# Black_jr5.net
KiCad netlist of a schematic drawn in EAGLE
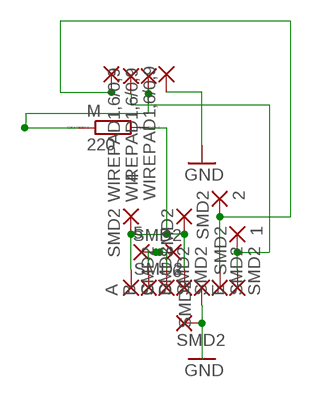
[diagram p0: schematic, sheet 1]

(export (version "E")
  (design (tool "Eeschema 10.0.6"))
  (components
    (comp (ref "+")
      (value "SMD2")
      (footprint "eagle-import:SMD1,27-2,54")
      (libsource (lib "eagle-import") (part "SMD2"))
    )
    (comp (ref "-")
      (value "SMD2")
      (footprint "eagle-import:SMD1,27-2,54")
      (libsource (lib "eagle-import") (part "SMD2"))
    )
    (comp (ref "--")
      (value "1,6/0,9")
      (footprint "eagle-import:1,6_0,9")
      (libsource (lib "eagle-import") (part "1,6/0,9"))
    )
    (comp (ref "---")
      (value "WIREPAD1,6/0,9")
      (footprint "eagle-import:1,6_0,9")
      (libsource (lib "eagle-import") (part "WIREPAD1,6/0,9"))
    )
    (comp (ref "----")
      (value "WIREPAD1,6/0,9")
      (footprint "eagle-import:1,6_0,9")
      (libsource (lib "eagle-import") (part "WIREPAD1,6/0,9"))
    )
    (comp (ref "-----")
      (value "WIREPAD1,6/0,9")
      (footprint "eagle-import:1,6_0,9")
      (libsource (lib "eagle-import") (part "WIREPAD1,6/0,9"))
    )
    (comp (ref "...")
      (value "SMD2")
      (footprint "eagle-import:SMD1,27-2,54")
      (libsource (lib "eagle-import") (part "SMD2"))
    )
    (comp (ref "1")
      (value "SMD2")
      (footprint "eagle-import:SMD1,27-2,54")
      (libsource (lib "eagle-import") (part "SMD2"))
    )
    (comp (ref "2")
      (value "SMD2")
      (footprint "eagle-import:SMD1,27-2,54")
      (libsource (lib "eagle-import") (part "SMD2"))
    )
    (comp (ref "4")
      (value "SMD2")
      (footprint "eagle-import:SMD1,27-2,54")
      (libsource (lib "eagle-import") (part "SMD2"))
    )
    (comp (ref "5")
      (value "SMD2")
      (footprint "eagle-import:SMD1,27-2,54")
      (libsource (lib "eagle-import") (part "SMD2"))
    )
    (comp (ref "6")
      (value "SMD2")
      (footprint "eagle-import:SMD1,27-2,54")
      (libsource (lib "eagle-import") (part "SMD2"))
    )
    (comp (ref "A")
      (value "SMD2")
      (footprint "eagle-import:SMD1,27-2,54")
      (libsource (lib "eagle-import") (part "SMD2"))
    )
    (comp (ref "B")
      (value "SMD2")
      (footprint "eagle-import:SMD1,27-2,54")
      (libsource (lib "eagle-import") (part "SMD2"))
    )
    (comp (ref "C")
      (value "SMD2")
      (footprint "eagle-import:SMD1,27-2,54")
      (libsource (lib "eagle-import") (part "SMD2"))
    )
    (comp (ref "D")
      (value "SMD2")
      (footprint "eagle-import:SMD1,27-2,54")
      (libsource (lib "eagle-import") (part "SMD2"))
    )
    (comp (ref "E")
      (value "SMD2")
      (footprint "eagle-import:SMD1,27-2,54")
      (libsource (lib "eagle-import") (part "SMD2"))
    )
    (comp (ref "M")
      (value "220")
      (footprint "eagle-import:0204_7")
      (libsource (lib "eagle-import") (part "R0204/7"))
    )
    (comp (ref "PAD7")
      (value "SMD2")
      (footprint "eagle-import:SMD1,27-2,54")
      (libsource (lib "eagle-import") (part "SMD2"))
    )
  )
  (nets
    (net (code "1") (name "GND") (class "Default")
      (node (ref "-") (pin "1") (pinfunction "P_1") (pintype "passive"))
      (node (ref "-----") (pin "1") (pinfunction "P_1") (pintype "passive"))
      (node (ref "PAD7") (pin "1") (pinfunction "P_1") (pintype "passive"))
    )
    (net (code "2") (name "Net-(+-P)") (class "Default")
      (node (ref "+") (pin "1") (pinfunction "P_1") (pintype "passive"))
      (node (ref "--") (pin "1") (pinfunction "P_1") (pintype "passive"))
      (node (ref "2") (pin "1") (pinfunction "P_1") (pintype "passive"))
    )
    (net (code "3") (name "Net-(-----P)") (class "Default")
      (node (ref "----") (pin "1") (pinfunction "P_1") (pintype "passive"))
      (node (ref "M") (pin "1") (pinfunction "1_1") (pintype "passive"))
    )
    (net (code "4") (name "Net-(----P)") (class "Default")
      (node (ref "---") (pin "1") (pinfunction "P_1") (pintype "passive"))
      (node (ref "1") (pin "1") (pinfunction "P_1") (pintype "passive"))
      (node (ref "E") (pin "1") (pinfunction "P_1") (pintype "passive"))
    )
    (net (code "5") (name "Net-(...-P)") (class "Default")
      (node (ref "...") (pin "1") (pinfunction "P_1") (pintype "passive"))
      (node (ref "4") (pin "1") (pinfunction "P_1") (pintype "passive"))
      (node (ref "A") (pin "1") (pinfunction "P_1") (pintype "passive"))
      (node (ref "D") (pin "1") (pinfunction "P_1") (pintype "passive"))
      (node (ref "M") (pin "2") (pinfunction "2_2") (pintype "passive"))
    )
    (net (code "6") (name "Net-(5-P)") (class "Default")
      (node (ref "5") (pin "1") (pinfunction "P_1") (pintype "passive"))
      (node (ref "6") (pin "1") (pinfunction "P_1") (pintype "passive"))
      (node (ref "B") (pin "1") (pinfunction "P_1") (pintype "passive"))
      (node (ref "C") (pin "1") (pinfunction "P_1") (pintype "passive"))
    )
  )
)
